# 408_jetracer_ledappend_boardRev010100.net
KiCad netlist of a schematic drawn in EAGLE
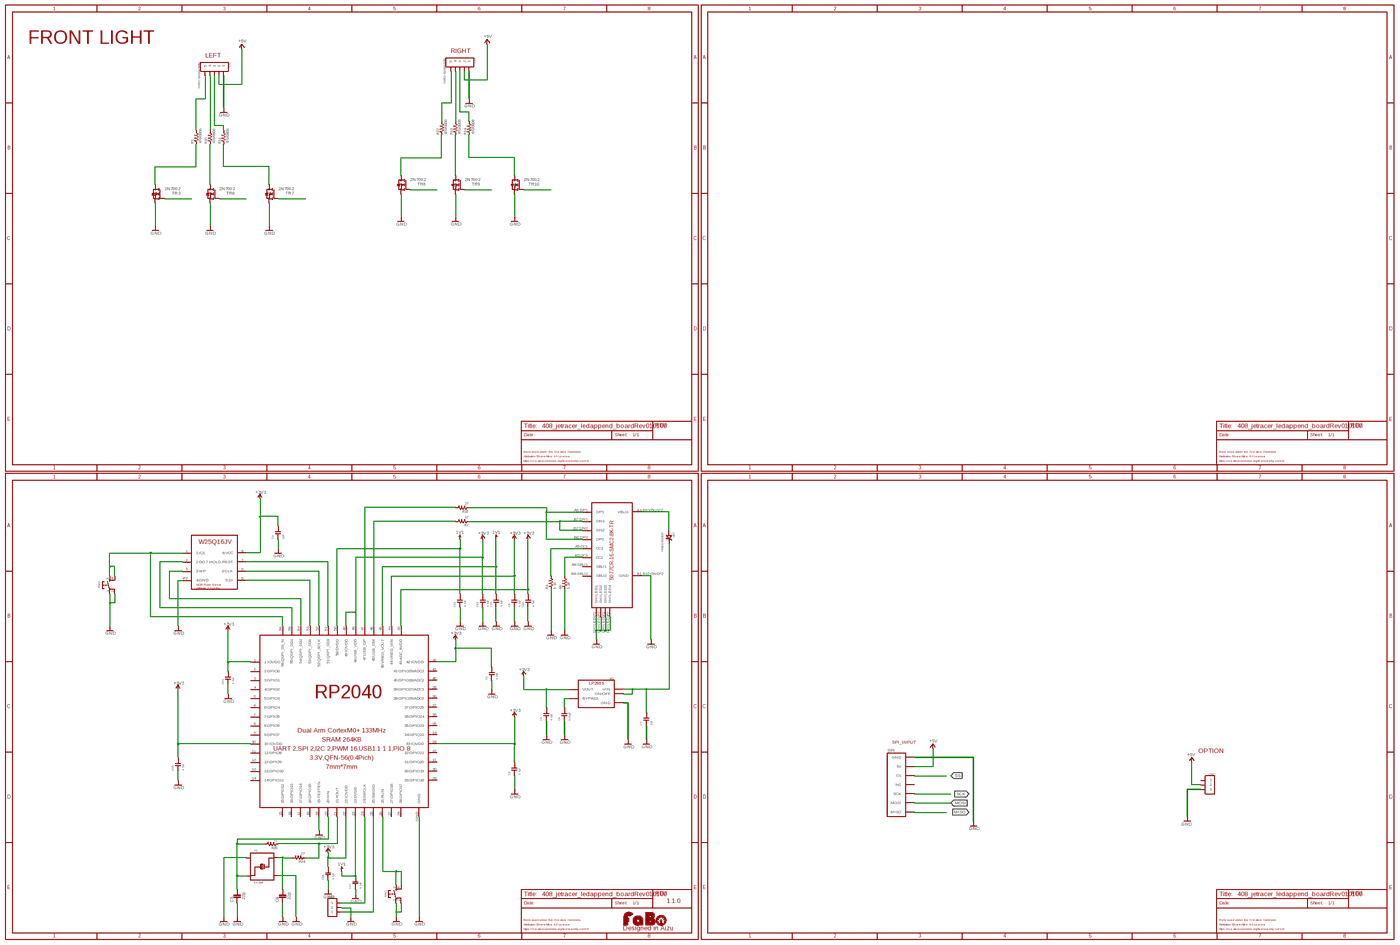
[diagram p0: schematic, sheet 1, overview]
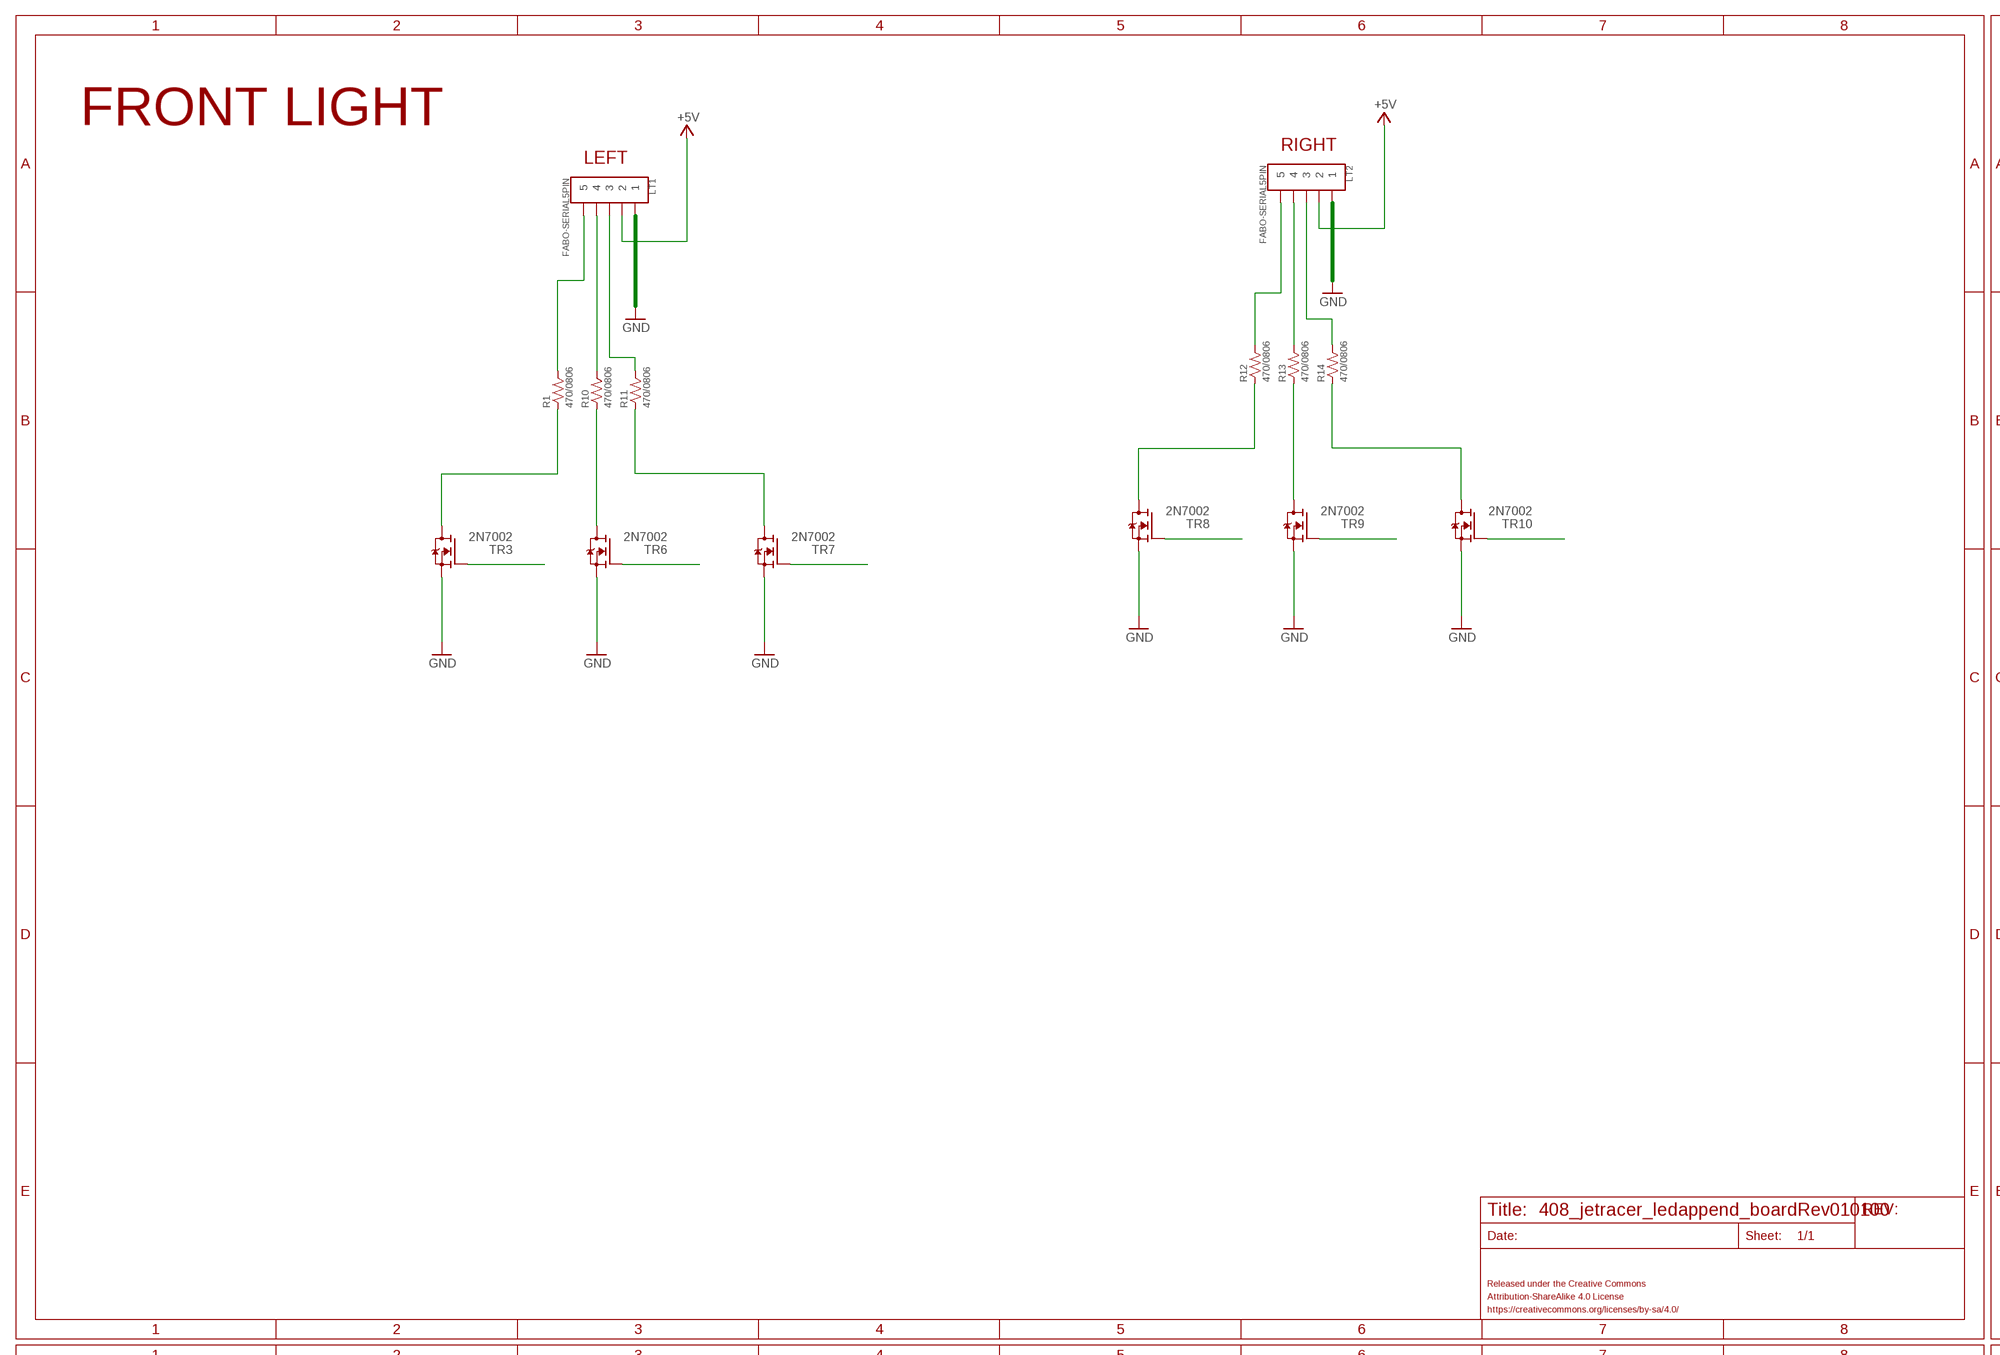
[diagram p1: schematic, sheet 1, part 1 of 4]
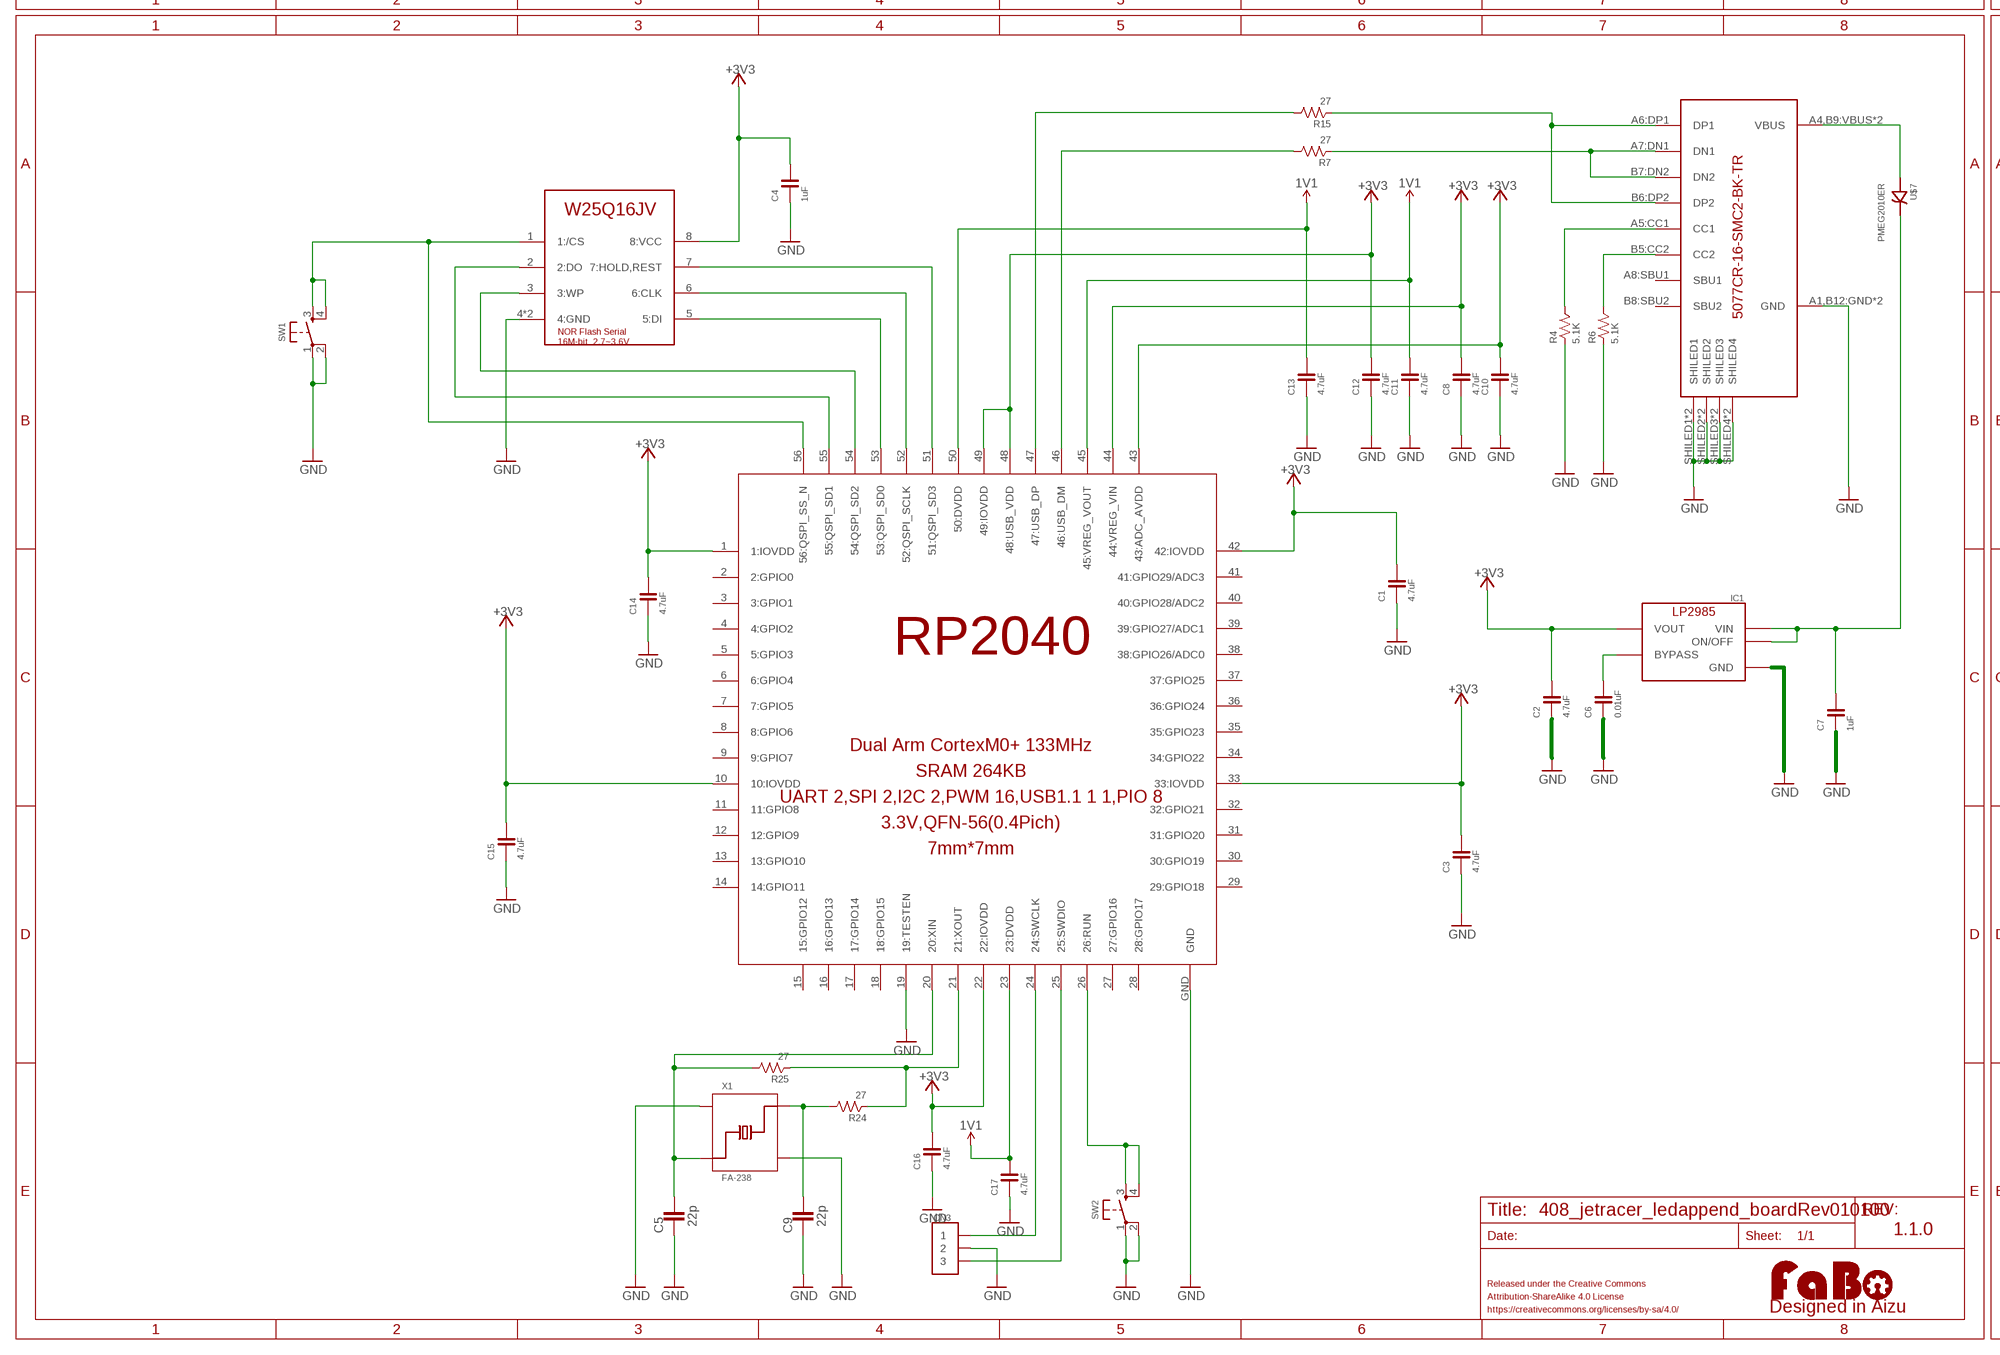
[diagram p2: schematic, sheet 1, part 2 of 4]
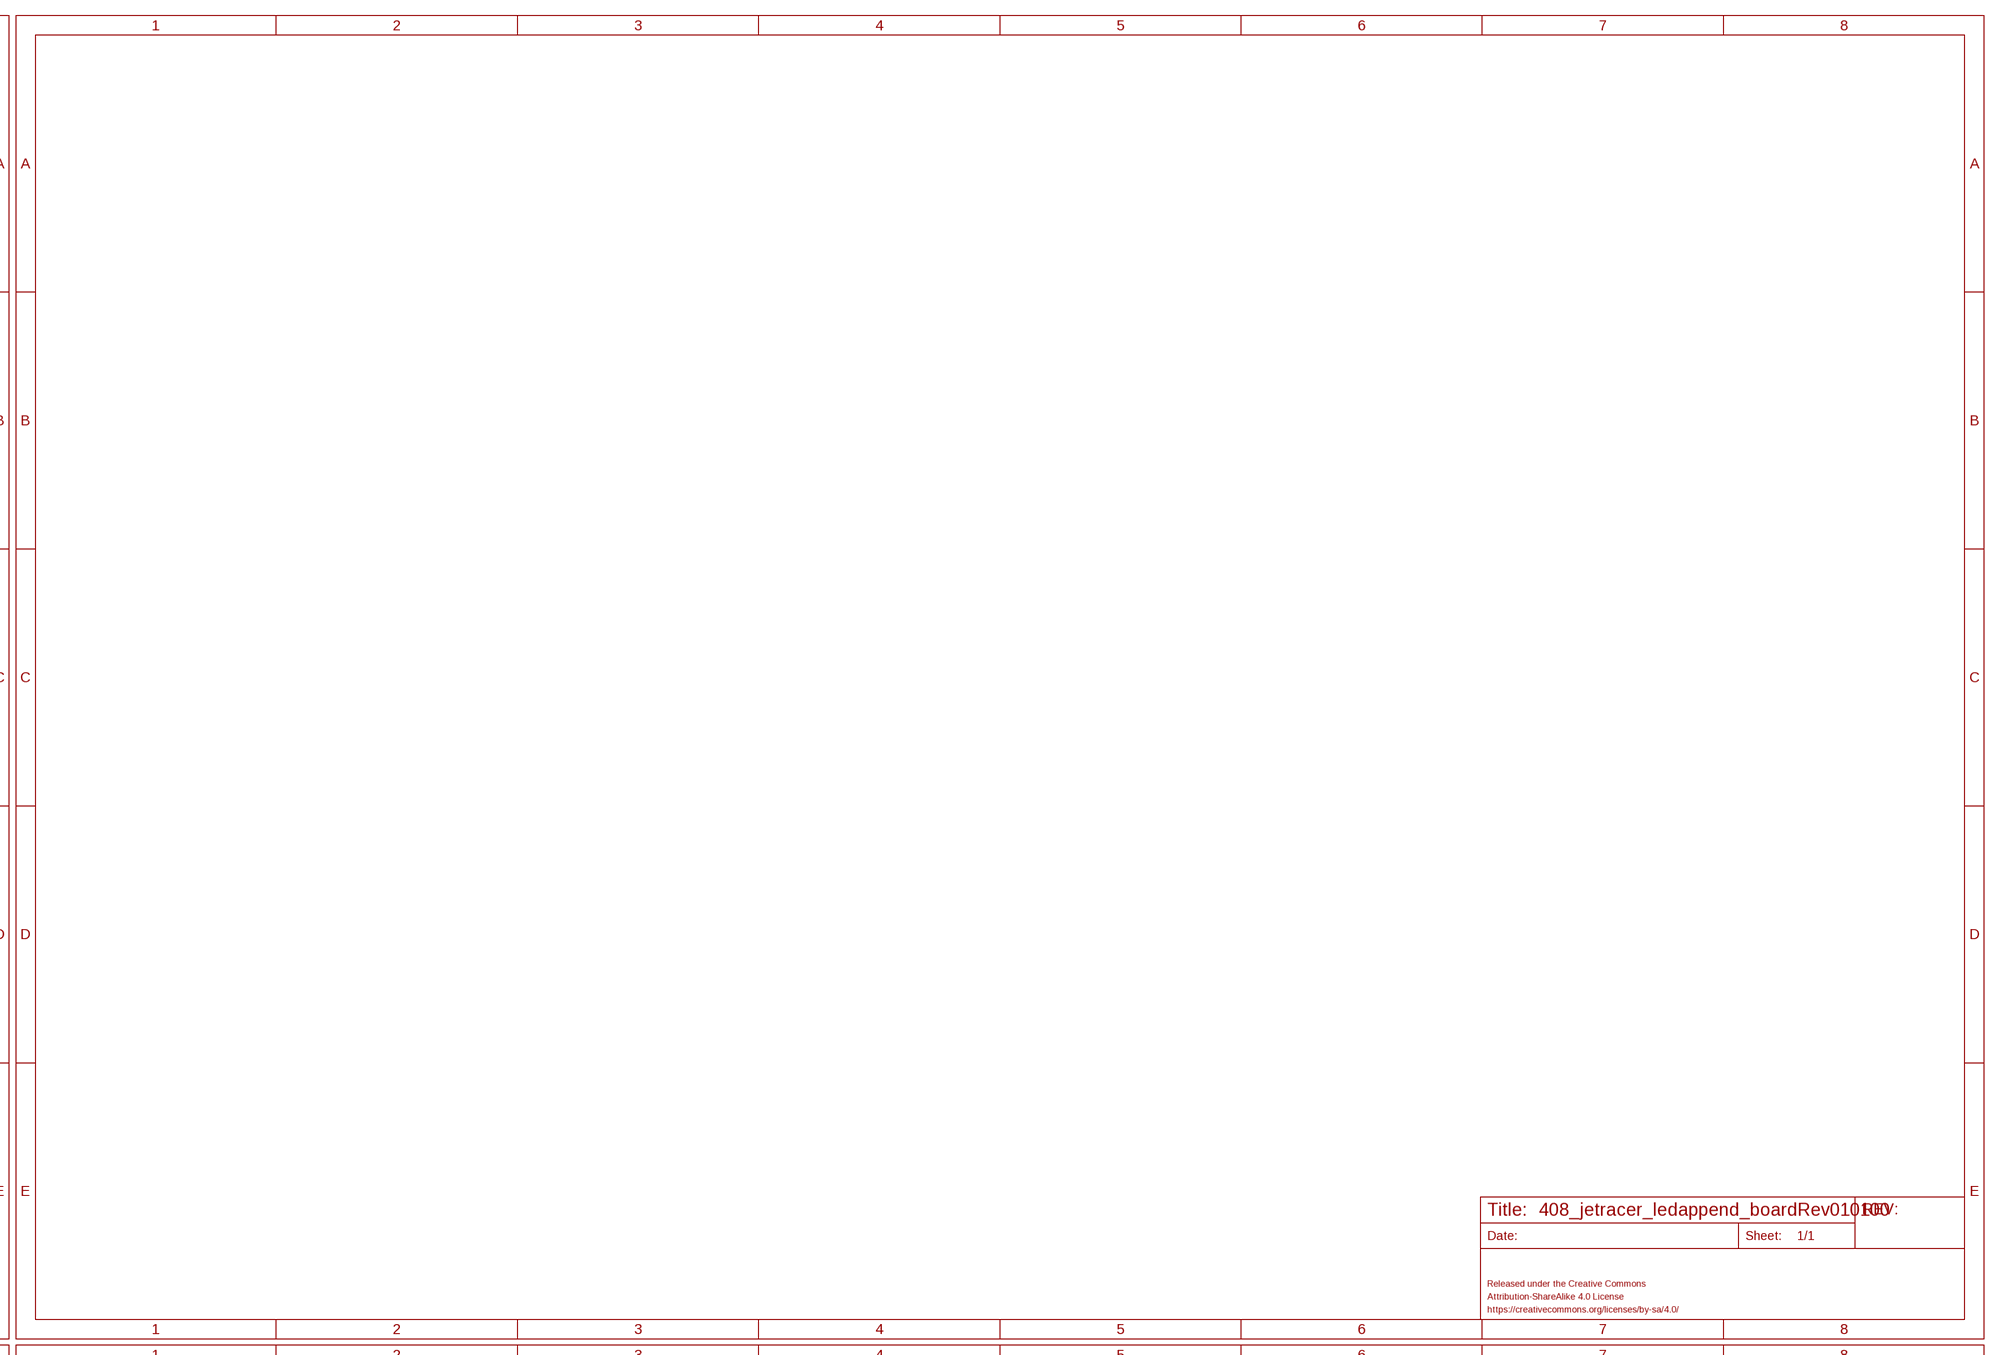
[diagram p3: schematic, sheet 1, part 3 of 4]
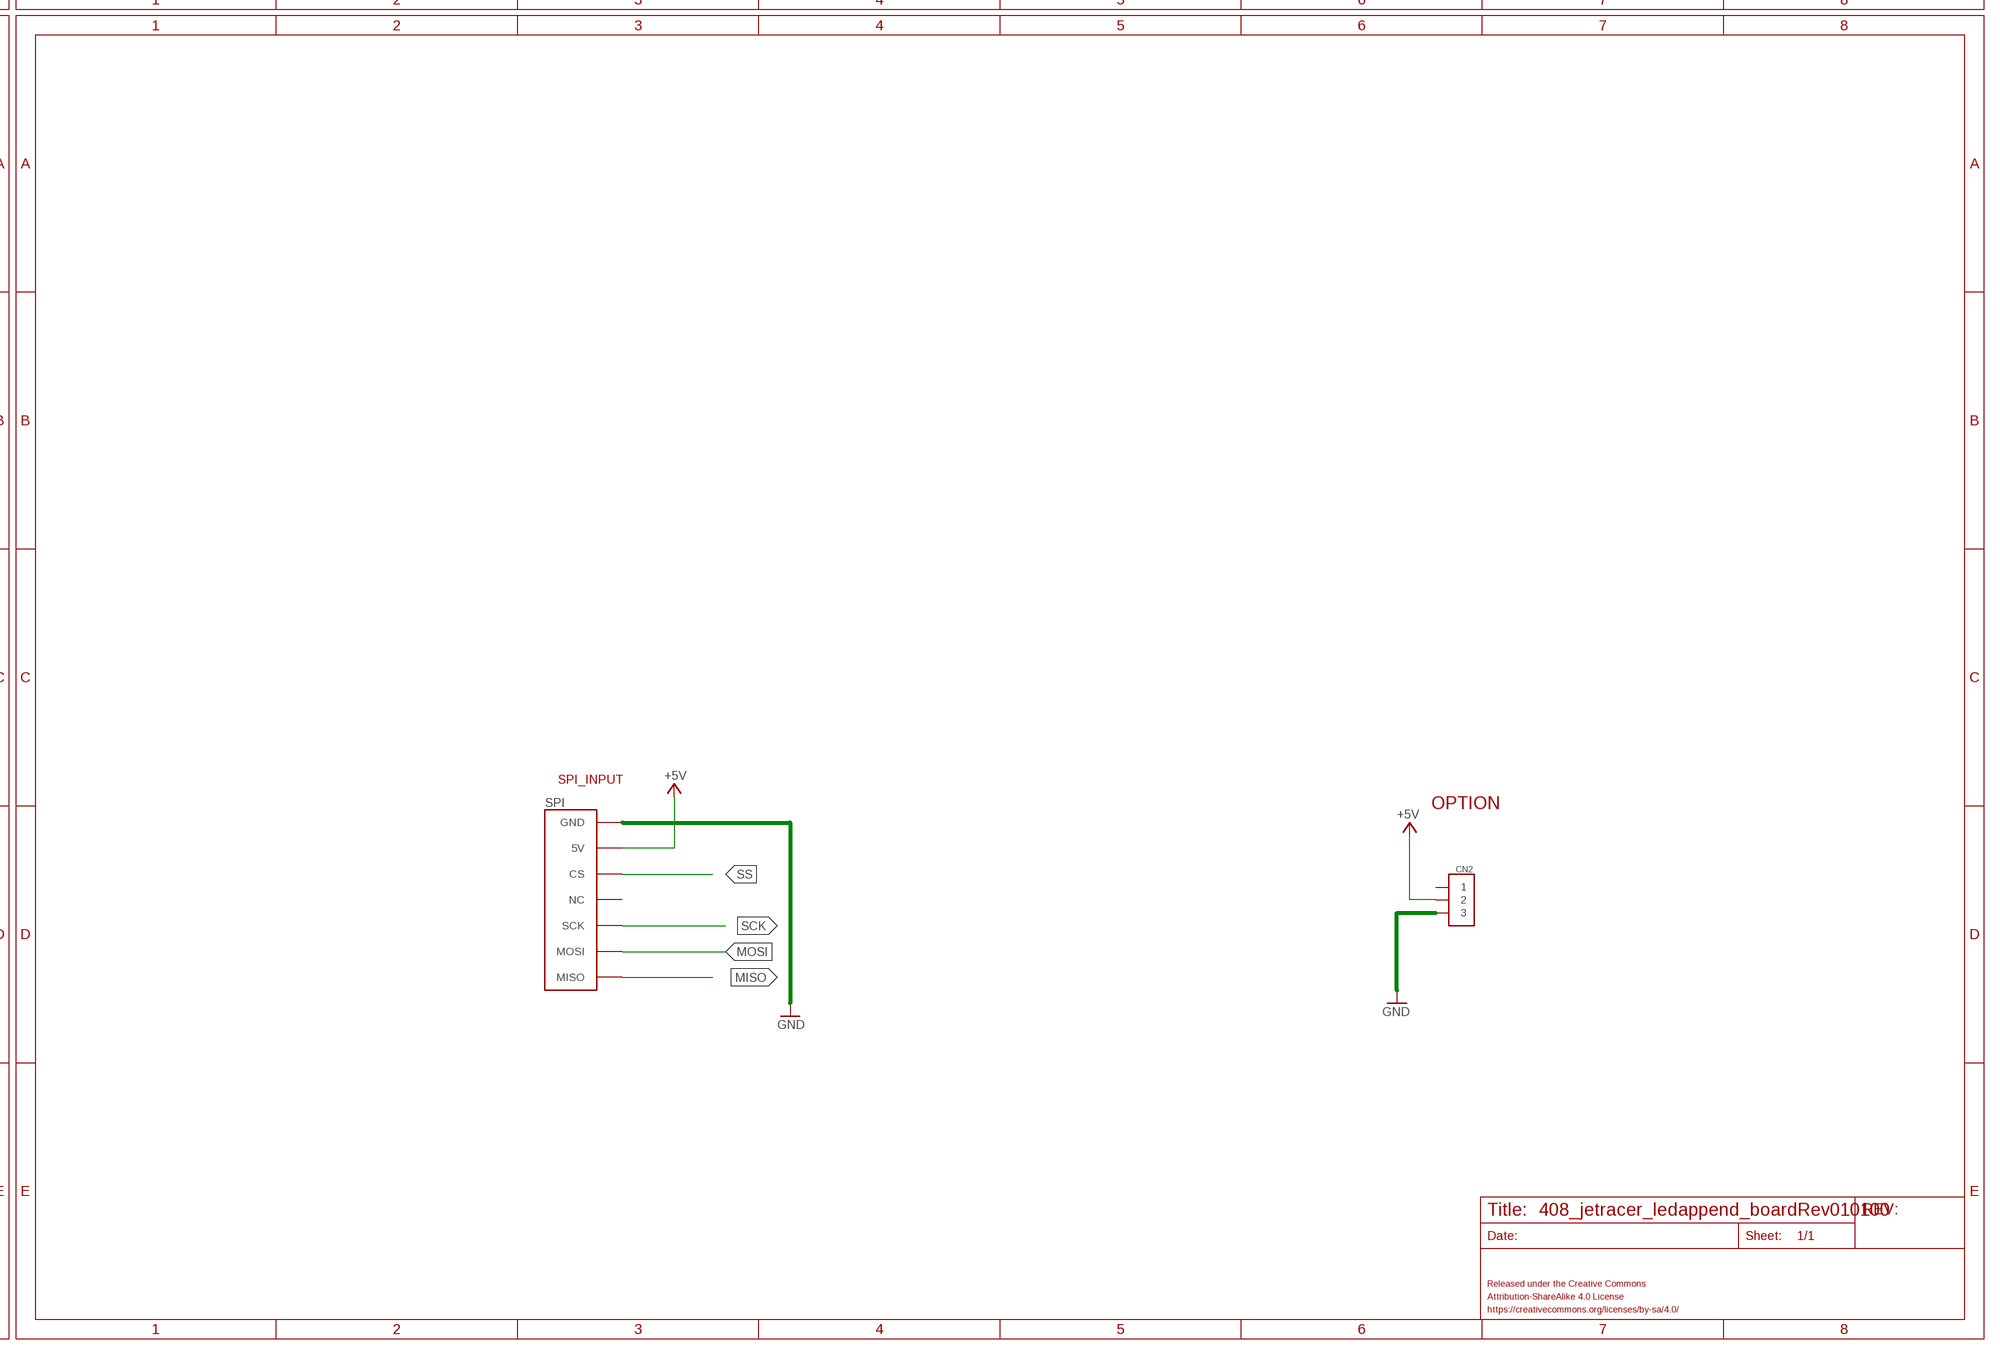
[diagram p4: schematic, sheet 1, part 4 of 4]

(export (version "E")
  (design (tool "Eeschema 10.0.6"))
  (components
    (comp (ref "C1")
      (value "4.7uF")
      (footprint "eagle-import:0603")
      (libsource (lib "eagle-import") (part "CAPACITOR-0603"))
    )
    (comp (ref "C2")
      (value "4.7uF")
      (footprint "eagle-import:0603")
      (libsource (lib "eagle-import") (part "CAPACITOR-0603"))
    )
    (comp (ref "C3")
      (value "4.7uF")
      (footprint "eagle-import:0603")
      (libsource (lib "eagle-import") (part "CAPACITOR-0603"))
    )
    (comp (ref "C4")
      (value "1uF")
      (footprint "eagle-import:0603")
      (libsource (lib "eagle-import") (part "CAPACITOR-0603"))
    )
    (comp (ref "C5")
      (value "22p")
      (footprint "eagle-import:C0603-ROUND")
      (fields (field (name "PART_NUMBER") "22pF_0603"))
      (libsource (lib "eagle-import") (part "0014_22PF_0603"))
    )
    (comp (ref "C6")
      (value "0.01uF")
      (footprint "eagle-import:0603")
      (libsource (lib "eagle-import") (part "CAPACITOR-0603"))
    )
    (comp (ref "C7")
      (value "1uF")
      (footprint "eagle-import:0603")
      (libsource (lib "eagle-import") (part "CAPACITOR-0603"))
    )
    (comp (ref "C8")
      (value "4.7uF")
      (footprint "eagle-import:0603")
      (libsource (lib "eagle-import") (part "CAPACITOR-0603"))
    )
    (comp (ref "C9")
      (value "22p")
      (footprint "eagle-import:C0603-ROUND")
      (fields (field (name "PART_NUMBER") "22pF_0603"))
      (libsource (lib "eagle-import") (part "0014_22PF_0603"))
    )
    (comp (ref "C10")
      (value "4.7uF")
      (footprint "eagle-import:0603")
      (libsource (lib "eagle-import") (part "CAPACITOR-0603"))
    )
    (comp (ref "C11")
      (value "4.7uF")
      (footprint "eagle-import:0603")
      (libsource (lib "eagle-import") (part "CAPACITOR-0603"))
    )
    (comp (ref "C12")
      (value "4.7uF")
      (footprint "eagle-import:0603")
      (libsource (lib "eagle-import") (part "CAPACITOR-0603"))
    )
    (comp (ref "C13")
      (value "4.7uF")
      (footprint "eagle-import:0603")
      (libsource (lib "eagle-import") (part "CAPACITOR-0603"))
    )
    (comp (ref "C14")
      (value "4.7uF")
      (footprint "eagle-import:0603")
      (libsource (lib "eagle-import") (part "CAPACITOR-0603"))
    )
    (comp (ref "C15")
      (value "4.7uF")
      (footprint "eagle-import:0603")
      (libsource (lib "eagle-import") (part "CAPACITOR-0603"))
    )
    (comp (ref "C16")
      (value "4.7uF")
      (footprint "eagle-import:0603")
      (libsource (lib "eagle-import") (part "CAPACITOR-0603"))
    )
    (comp (ref "C17")
      (value "4.7uF")
      (footprint "eagle-import:0603")
      (libsource (lib "eagle-import") (part "CAPACITOR-0603"))
    )
    (comp (ref "CN2")
      (value "PIN_1X3")
      (footprint "eagle-import:PIN_1X3")
      (libsource (lib "eagle-import") (part "PIN_1X3"))
    )
    (comp (ref "CN3")
      (value "PIN_1X3")
      (footprint "eagle-import:PIN_1X3")
      (libsource (lib "eagle-import") (part "PIN_1X3"))
    )
    (comp (ref "IC1")
      (value "LP2985-33DBV")
      (footprint "eagle-import:SOT-23-5")
      (libsource (lib "eagle-import") (part "LP2985-33DBV"))
    )
    (comp (ref "LOGO2")
      (value "LOGO_FABO-M_BOTTOM")
      (footprint "eagle-import:LOGO_FABO_M_BOTTOM")
      (libsource (lib "eagle-import") (part "LOGO_FABO-M_BOTTOM"))
    )
    (comp (ref "LT1")
      (value "FABO-SERIAL5PIN")
      (footprint "eagle-import:BM05B-PASS-1")
      (libsource (lib "eagle-import") (part "FABO-SERIAL5PIN"))
    )
    (comp (ref "LT2")
      (value "FABO-SERIAL5PIN")
      (footprint "eagle-import:BM05B-PASS-1")
      (libsource (lib "eagle-import") (part "FABO-SERIAL5PIN"))
    )
    (comp (ref "R1")
      (value "470/0806")
      (footprint "eagle-import:0805")
      (libsource (lib "eagle-import") (part "RESISTOR-0805"))
    )
    (comp (ref "R4")
      (value "5.1K")
      (footprint "eagle-import:0603")
      (libsource (lib "eagle-import") (part "RESISTOR-0603"))
    )
    (comp (ref "R6")
      (value "5.1K")
      (footprint "eagle-import:0603")
      (libsource (lib "eagle-import") (part "RESISTOR-0603"))
    )
    (comp (ref "R7")
      (value "27")
      (footprint "eagle-import:0603")
      (libsource (lib "eagle-import") (part "RESISTOR-0603"))
    )
    (comp (ref "R10")
      (value "470/0806")
      (footprint "eagle-import:0805")
      (libsource (lib "eagle-import") (part "RESISTOR-0805"))
    )
    (comp (ref "R11")
      (value "470/0806")
      (footprint "eagle-import:0805")
      (libsource (lib "eagle-import") (part "RESISTOR-0805"))
    )
    (comp (ref "R12")
      (value "470/0806")
      (footprint "eagle-import:0805")
      (libsource (lib "eagle-import") (part "RESISTOR-0805"))
    )
    (comp (ref "R13")
      (value "470/0806")
      (footprint "eagle-import:0805")
      (libsource (lib "eagle-import") (part "RESISTOR-0805"))
    )
    (comp (ref "R14")
      (value "470/0806")
      (footprint "eagle-import:0805")
      (libsource (lib "eagle-import") (part "RESISTOR-0805"))
    )
    (comp (ref "R15")
      (value "27")
      (footprint "eagle-import:0603")
      (libsource (lib "eagle-import") (part "RESISTOR-0603"))
    )
    (comp (ref "R24")
      (value "27")
      (footprint "eagle-import:0603")
      (libsource (lib "eagle-import") (part "RESISTOR-0603"))
    )
    (comp (ref "R25")
      (value "27")
      (footprint "eagle-import:0603")
      (libsource (lib "eagle-import") (part "RESISTOR-0603"))
    )
    (comp (ref "SPI")
      (value "FABO-7PINMULTI_SPI")
      (footprint "eagle-import:BM07B-PASS-1")
      (libsource (lib "eagle-import") (part "FABO-7PINMULTI_SPI"))
    )
    (comp (ref "SW1")
      (value "TACT-SWITCH-SMD_KMR2")
      (footprint "eagle-import:KMR2")
      (libsource (lib "eagle-import") (part "TACT-SWITCH-SMD_KMR2"))
    )
    (comp (ref "SW2")
      (value "TACT-SWITCH-SMD_KMR2")
      (footprint "eagle-import:KMR2")
      (libsource (lib "eagle-import") (part "TACT-SWITCH-SMD_KMR2"))
    )
    (comp (ref "TR3")
      (value "2N7002")
      (footprint "eagle-import:SOT-23")
      (libsource (lib "eagle-import") (part "1612_2N7002LT1G"))
    )
    (comp (ref "TR6")
      (value "2N7002")
      (footprint "eagle-import:SOT-23")
      (libsource (lib "eagle-import") (part "1612_2N7002LT1G"))
    )
    (comp (ref "TR7")
      (value "2N7002")
      (footprint "eagle-import:SOT-23")
      (libsource (lib "eagle-import") (part "1612_2N7002LT1G"))
    )
    (comp (ref "TR8")
      (value "2N7002")
      (footprint "eagle-import:SOT-23")
      (libsource (lib "eagle-import") (part "1612_2N7002LT1G"))
    )
    (comp (ref "TR9")
      (value "2N7002")
      (footprint "eagle-import:SOT-23")
      (libsource (lib "eagle-import") (part "1612_2N7002LT1G"))
    )
    (comp (ref "TR10")
      (value "2N7002")
      (footprint "eagle-import:SOT-23")
      (libsource (lib "eagle-import") (part "1612_2N7002LT1G"))
    )
    (comp (ref "U$2")
      (value "RP2040")
      (footprint "eagle-import:RP2040")
      (libsource (lib "eagle-import") (part "RP2040"))
    )
    (comp (ref "U$4")
      (value "W25Q16JVZPIM")
      (footprint "eagle-import:WSON8")
      (libsource (lib "eagle-import") (part "W25Q16JVZPIM"))
    )
    (comp (ref "U$6")
      (value "5077CR-16-SMC2-BK-TR")
      (footprint "eagle-import:5077CR-16-SMC2-BK-TR")
      (libsource (lib "eagle-import") (part "5077CR-16-SMC2-BK-TR"))
    )
    (comp (ref "U$7")
      (value "PMEG2010ER")
      (footprint "eagle-import:SOD123W")
      (libsource (lib "eagle-import") (part "PMEG2010ER"))
    )
    (comp (ref "X1")
      (value "FA-238")
      (footprint "eagle-import:FA-238")
      (libsource (lib "eagle-import") (part "FA-238"))
    )
  )
  (nets
    (net (code "1") (name "+3V3") (class "Default")
      (node (ref "C1") (pin "2") (pinfunction "2_2") (pintype "passive"))
      (node (ref "C10") (pin "2") (pinfunction "2_2") (pintype "passive"))
      (node (ref "C12") (pin "2") (pinfunction "2_2") (pintype "passive"))
      (node (ref "C14") (pin "2") (pinfunction "2_2") (pintype "passive"))
      (node (ref "C15") (pin "2") (pinfunction "2_2") (pintype "passive"))
      (node (ref "C16") (pin "2") (pinfunction "2_2") (pintype "passive"))
      (node (ref "C2") (pin "2") (pinfunction "2_2") (pintype "passive"))
      (node (ref "C3") (pin "2") (pinfunction "2_2") (pintype "passive"))
      (node (ref "C4") (pin "2") (pinfunction "2_2") (pintype "passive"))
      (node (ref "C8") (pin "2") (pinfunction "2_2") (pintype "passive"))
      (node (ref "IC1") (pin "5") (pinfunction "VOUT_5") (pintype "output"))
      (node (ref "U$2") (pin "1") (pinfunction "1:IOVDD_1") (pintype "bidirectional"))
      (node (ref "U$2") (pin "10") (pinfunction "10:IOVDD_10") (pintype "bidirectional"))
      (node (ref "U$2") (pin "22") (pinfunction "22:IOVDD_22") (pintype "bidirectional"))
      (node (ref "U$2") (pin "33") (pinfunction "33:IOVDD_33") (pintype "bidirectional"))
      (node (ref "U$2") (pin "42") (pinfunction "42:IOVDD_42") (pintype "bidirectional"))
      (node (ref "U$2") (pin "43") (pinfunction "43:ADC_AVDD_43") (pintype "bidirectional"))
      (node (ref "U$2") (pin "44") (pinfunction "44:VREG_VIN_44") (pintype "bidirectional"))
      (node (ref "U$2") (pin "48") (pinfunction "48:USB_VDD_48") (pintype "bidirectional"))
      (node (ref "U$2") (pin "49") (pinfunction "49:IOVDD_49") (pintype "bidirectional"))
      (node (ref "U$4") (pin "8") (pinfunction "8:VCC_8") (pintype "power_in"))
    )
    (net (code "2") (name "+5V") (class "Default")
      (node (ref "CN2") (pin "2") (pinfunction "2_2") (pintype "bidirectional"))
      (node (ref "LT1") (pin "2") (pinfunction "2_2") (pintype "bidirectional"))
      (node (ref "LT2") (pin "2") (pinfunction "2_2") (pintype "bidirectional"))
      (node (ref "SPI") (pin "2") (pinfunction "5V_2") (pintype "bidirectional"))
    )
    (net (code "3") (name "/N$10") (class "Default")
      (node (ref "TR10") (pin "3") (pinfunction "G_3") (pintype "passive"))
      (node (ref "TR3") (pin "3") (pinfunction "G_3") (pintype "passive"))
      (node (ref "TR6") (pin "3") (pinfunction "G_3") (pintype "passive"))
      (node (ref "TR7") (pin "3") (pinfunction "G_3") (pintype "passive"))
      (node (ref "TR8") (pin "3") (pinfunction "G_3") (pintype "passive"))
      (node (ref "TR9") (pin "3") (pinfunction "G_3") (pintype "passive"))
    )
    (net (code "4") (name "1V1") (class "Default")
      (node (ref "C11") (pin "2") (pinfunction "2_2") (pintype "passive"))
      (node (ref "C13") (pin "2") (pinfunction "2_2") (pintype "passive"))
      (node (ref "C17") (pin "2") (pinfunction "2_2") (pintype "passive"))
      (node (ref "U$2") (pin "23") (pinfunction "23:DVDD_23") (pintype "bidirectional"))
      (node (ref "U$2") (pin "45") (pinfunction "45:VREG_VOUT_45") (pintype "bidirectional"))
      (node (ref "U$2") (pin "50") (pinfunction "50:DVDD_50") (pintype "bidirectional"))
    )
    (net (code "5") (name "GND") (class "Default")
      (node (ref "C1") (pin "1") (pinfunction "1_1") (pintype "passive"))
      (node (ref "C10") (pin "1") (pinfunction "1_1") (pintype "passive"))
      (node (ref "C11") (pin "1") (pinfunction "1_1") (pintype "passive"))
      (node (ref "C12") (pin "1") (pinfunction "1_1") (pintype "passive"))
      (node (ref "C13") (pin "1") (pinfunction "1_1") (pintype "passive"))
      (node (ref "C14") (pin "1") (pinfunction "1_1") (pintype "passive"))
      (node (ref "C15") (pin "1") (pinfunction "1_1") (pintype "passive"))
      (node (ref "C16") (pin "1") (pinfunction "1_1") (pintype "passive"))
      (node (ref "C17") (pin "1") (pinfunction "1_1") (pintype "passive"))
      (node (ref "C2") (pin "1") (pinfunction "1_1") (pintype "passive"))
      (node (ref "C3") (pin "1") (pinfunction "1_1") (pintype "passive"))
      (node (ref "C4") (pin "1") (pinfunction "1_1") (pintype "passive"))
      (node (ref "C5") (pin "1") (pinfunction "1_1") (pintype "passive"))
      (node (ref "C6") (pin "1") (pinfunction "1_1") (pintype "passive"))
      (node (ref "C7") (pin "1") (pinfunction "1_1") (pintype "passive"))
      (node (ref "C8") (pin "1") (pinfunction "1_1") (pintype "passive"))
      (node (ref "C9") (pin "1") (pinfunction "1_1") (pintype "passive"))
      (node (ref "CN2") (pin "3") (pinfunction "3_3") (pintype "bidirectional"))
      (node (ref "CN3") (pin "2") (pinfunction "2_2") (pintype "bidirectional"))
      (node (ref "IC1") (pin "2") (pinfunction "GND_2") (pintype "power_in"))
      (node (ref "LT1") (pin "1") (pinfunction "1_1") (pintype "bidirectional"))
      (node (ref "LT2") (pin "1") (pinfunction "1_1") (pintype "bidirectional"))
      (node (ref "R4") (pin "1") (pinfunction "1_1") (pintype "bidirectional"))
      (node (ref "R6") (pin "1") (pinfunction "1_1") (pintype "bidirectional"))
      (node (ref "SPI") (pin "1") (pinfunction "GND_1") (pintype "bidirectional"))
      (node (ref "SW1") (pin "1") (pinfunction "1_1") (pintype "passive"))
      (node (ref "SW1") (pin "2") (pinfunction "2_2") (pintype "passive"))
      (node (ref "SW2") (pin "1") (pinfunction "1_1") (pintype "passive"))
      (node (ref "SW2") (pin "2") (pinfunction "2_2") (pintype "passive"))
      (node (ref "TR10") (pin "2") (pinfunction "S_2") (pintype "passive"))
      (node (ref "TR3") (pin "2") (pinfunction "S_2") (pintype "passive"))
      (node (ref "TR6") (pin "2") (pinfunction "S_2") (pintype "passive"))
      (node (ref "TR7") (pin "2") (pinfunction "S_2") (pintype "passive"))
      (node (ref "TR8") (pin "2") (pinfunction "S_2") (pintype "passive"))
      (node (ref "TR9") (pin "2") (pinfunction "S_2") (pintype "passive"))
      (node (ref "U$2") (pin "19") (pinfunction "19:TESTEN_19") (pintype "bidirectional"))
      (node (ref "U$2") (pin "GND") (pinfunction "GND_GND") (pintype "bidirectional"))
      (node (ref "U$4") (pin "4") (pinfunction "4:GND_4") (pintype "power_in"))
      (node (ref "U$4") (pin "PAD") (pinfunction "4:GND_PAD") (pintype "power_in"))
      (node (ref "U$6") (pin "A1,B12:GND") (pinfunction "GND_A1,B12:GND") (pintype "power_in"))
      (node (ref "U$6") (pin "B1,A12:GND") (pinfunction "GND_B1,A12:GND") (pintype "power_in"))
      (node (ref "U$6") (pin "SHILED1") (pinfunction "SHILED1_SHILED1") (pintype "bidirectional"))
      (node (ref "U$6") (pin "SHILED2") (pinfunction "SHILED2_SHILED2") (pintype "bidirectional"))
      (node (ref "U$6") (pin "SHILED3") (pinfunction "SHILED3_SHILED3") (pintype "bidirectional"))
      (node (ref "U$6") (pin "SHILED4") (pinfunction "SHILED4_SHILED4") (pintype "bidirectional"))
      (node (ref "U$6") (pin "SHILED5") (pinfunction "SHILED1_SHILED5") (pintype "bidirectional"))
      (node (ref "U$6") (pin "SHILED6") (pinfunction "SHILED2_SHILED6") (pintype "bidirectional"))
      (node (ref "U$6") (pin "SHILED7") (pinfunction "SHILED3_SHILED7") (pintype "bidirectional"))
      (node (ref "U$6") (pin "SHILED8") (pinfunction "SHILED4_SHILED8") (pintype "bidirectional"))
      (node (ref "X1") (pin "2") (pinfunction "#2_2") (pintype "bidirectional"))
      (node (ref "X1") (pin "4") (pinfunction "#4_4") (pintype "bidirectional"))
    )
    (net (code "6") (name "MISO") (class "Default")
      (node (ref "SPI") (pin "7") (pinfunction "MISO_7") (pintype "bidirectional"))
    )
    (net (code "7") (name "MOSI") (class "Default")
      (node (ref "SPI") (pin "6") (pinfunction "MOSI_6") (pintype "bidirectional"))
    )
    (net (code "8") (name "Net-(IC1-BYPASS)") (class "Default")
      (node (ref "C6") (pin "2") (pinfunction "2_2") (pintype "passive"))
      (node (ref "IC1") (pin "4") (pinfunction "BYPASS_4") (pintype "bidirectional"))
    )
    (net (code "9") (name "Net-(IC1-ON{slash}OFF)") (class "Default")
      (node (ref "C7") (pin "2") (pinfunction "2_2") (pintype "passive"))
      (node (ref "IC1") (pin "1") (pinfunction "VIN_1") (pintype "input"))
      (node (ref "IC1") (pin "3") (pinfunction "ON/OFF_3") (pintype "input"))
      (node (ref "U$7") (pin "1") (pinfunction "CATHODE_1") (pintype "bidirectional"))
    )
    (net (code "10") (name "Net-(LT1-Pad3)") (class "Default")
      (node (ref "LT1") (pin "3") (pinfunction "3_3") (pintype "bidirectional"))
      (node (ref "R11") (pin "2") (pinfunction "2_2") (pintype "bidirectional"))
    )
    (net (code "11") (name "Net-(LT1-Pad4)") (class "Default")
      (node (ref "LT1") (pin "4") (pinfunction "4_4") (pintype "bidirectional"))
      (node (ref "R10") (pin "2") (pinfunction "2_2") (pintype "bidirectional"))
    )
    (net (code "12") (name "Net-(LT1-Pad5)") (class "Default")
      (node (ref "LT1") (pin "5") (pinfunction "5_5") (pintype "bidirectional"))
      (node (ref "R1") (pin "2") (pinfunction "2_2") (pintype "bidirectional"))
    )
    (net (code "13") (name "Net-(LT2-Pad3)") (class "Default")
      (node (ref "LT2") (pin "3") (pinfunction "3_3") (pintype "bidirectional"))
      (node (ref "R14") (pin "2") (pinfunction "2_2") (pintype "bidirectional"))
    )
    (net (code "14") (name "Net-(LT2-Pad4)") (class "Default")
      (node (ref "LT2") (pin "4") (pinfunction "4_4") (pintype "bidirectional"))
      (node (ref "R13") (pin "2") (pinfunction "2_2") (pintype "bidirectional"))
    )
    (net (code "15") (name "Net-(LT2-Pad5)") (class "Default")
      (node (ref "LT2") (pin "5") (pinfunction "5_5") (pintype "bidirectional"))
      (node (ref "R12") (pin "2") (pinfunction "2_2") (pintype "bidirectional"))
    )
    (net (code "16") (name "Net-(TR3-D)") (class "Default")
      (node (ref "R1") (pin "1") (pinfunction "1_1") (pintype "bidirectional"))
      (node (ref "TR3") (pin "1") (pinfunction "D_1") (pintype "passive"))
    )
    (net (code "17") (name "Net-(TR6-D)") (class "Default")
      (node (ref "R10") (pin "1") (pinfunction "1_1") (pintype "bidirectional"))
      (node (ref "TR6") (pin "1") (pinfunction "D_1") (pintype "passive"))
    )
    (net (code "18") (name "Net-(TR7-D)") (class "Default")
      (node (ref "R11") (pin "1") (pinfunction "1_1") (pintype "bidirectional"))
      (node (ref "TR7") (pin "1") (pinfunction "D_1") (pintype "passive"))
    )
    (net (code "19") (name "Net-(TR8-D)") (class "Default")
      (node (ref "R12") (pin "1") (pinfunction "1_1") (pintype "bidirectional"))
      (node (ref "TR8") (pin "1") (pinfunction "D_1") (pintype "passive"))
    )
    (net (code "20") (name "Net-(TR9-D)") (class "Default")
      (node (ref "R13") (pin "1") (pinfunction "1_1") (pintype "bidirectional"))
      (node (ref "TR9") (pin "1") (pinfunction "D_1") (pintype "passive"))
    )
    (net (code "21") (name "Net-(TR10-D)") (class "Default")
      (node (ref "R14") (pin "1") (pinfunction "1_1") (pintype "bidirectional"))
      (node (ref "TR10") (pin "1") (pinfunction "D_1") (pintype "passive"))
    )
    (net (code "22") (name "Net-(U$2-20:XIN)") (class "Default")
      (node (ref "C5") (pin "2") (pinfunction "2_2") (pintype "passive"))
      (node (ref "R25") (pin "2") (pinfunction "2_2") (pintype "bidirectional"))
      (node (ref "U$2") (pin "20") (pinfunction "20:XIN_20") (pintype "bidirectional"))
      (node (ref "X1") (pin "1") (pinfunction "#1_1") (pintype "bidirectional"))
    )
    (net (code "23") (name "Net-(U$2-21:XOUT)") (class "Default")
      (node (ref "R24") (pin "1") (pinfunction "1_1") (pintype "bidirectional"))
      (node (ref "R25") (pin "1") (pinfunction "1_1") (pintype "bidirectional"))
      (node (ref "U$2") (pin "21") (pinfunction "21:XOUT_21") (pintype "bidirectional"))
    )
    (net (code "24") (name "Net-(U$2-24:SWCLK)") (class "Default")
      (node (ref "CN3") (pin "1") (pinfunction "1_1") (pintype "bidirectional"))
      (node (ref "U$2") (pin "24") (pinfunction "24:SWCLK_24") (pintype "bidirectional"))
    )
    (net (code "25") (name "Net-(U$2-25:SWDIO)") (class "Default")
      (node (ref "CN3") (pin "3") (pinfunction "3_3") (pintype "bidirectional"))
      (node (ref "U$2") (pin "25") (pinfunction "25:SWDIO_25") (pintype "bidirectional"))
    )
    (net (code "26") (name "Net-(U$2-26:RUN)") (class "Default")
      (node (ref "SW2") (pin "3") (pinfunction "3_3") (pintype "passive"))
      (node (ref "SW2") (pin "4") (pinfunction "4_4") (pintype "passive"))
      (node (ref "U$2") (pin "26") (pinfunction "26:RUN_26") (pintype "bidirectional"))
    )
    (net (code "27") (name "Net-(U$2-46:USB_DM)") (class "Default")
      (node (ref "R7") (pin "2") (pinfunction "2_2") (pintype "bidirectional"))
      (node (ref "U$2") (pin "46") (pinfunction "46:USB_DM_46") (pintype "bidirectional"))
    )
    (net (code "28") (name "Net-(U$2-47:USB_DP)") (class "Default")
      (node (ref "R15") (pin "2") (pinfunction "2_2") (pintype "bidirectional"))
      (node (ref "U$2") (pin "47") (pinfunction "47:USB_DP_47") (pintype "bidirectional"))
    )
    (net (code "29") (name "Net-(U$2-51:QSPI_SD3)") (class "Default")
      (node (ref "U$2") (pin "51") (pinfunction "51:QSPI_SD3_51") (pintype "bidirectional"))
      (node (ref "U$4") (pin "7") (pinfunction "7:HOLD,REST_7") (pintype "bidirectional"))
    )
    (net (code "30") (name "Net-(U$2-52:QSPI_SCLK)") (class "Default")
      (node (ref "U$2") (pin "52") (pinfunction "52:QSPI_SCLK_52") (pintype "bidirectional"))
      (node (ref "U$4") (pin "6") (pinfunction "6:CLK_6") (pintype "input"))
    )
    (net (code "31") (name "Net-(U$2-53:QSPI_SD0)") (class "Default")
      (node (ref "U$2") (pin "53") (pinfunction "53:QSPI_SD0_53") (pintype "bidirectional"))
      (node (ref "U$4") (pin "5") (pinfunction "5:DI_5") (pintype "bidirectional"))
    )
    (net (code "32") (name "Net-(U$2-54:QSPI_SD2)") (class "Default")
      (node (ref "U$2") (pin "54") (pinfunction "54:QSPI_SD2_54") (pintype "bidirectional"))
      (node (ref "U$4") (pin "3") (pinfunction "3:WP_3") (pintype "bidirectional"))
    )
    (net (code "33") (name "Net-(U$2-55:QSPI_SD1)") (class "Default")
      (node (ref "U$2") (pin "55") (pinfunction "55:QSPI_SD1_55") (pintype "bidirectional"))
      (node (ref "U$4") (pin "2") (pinfunction "2:DO_2") (pintype "output"))
    )
    (net (code "34") (name "Net-(U$2-56:QSPI_SS_N)") (class "Default")
      (node (ref "SW1") (pin "3") (pinfunction "3_3") (pintype "passive"))
      (node (ref "SW1") (pin "4") (pinfunction "4_4") (pintype "passive"))
      (node (ref "U$2") (pin "56") (pinfunction "56:QSPI_SS_N_56") (pintype "bidirectional"))
      (node (ref "U$4") (pin "1") (pinfunction "1:/CS_1") (pintype "input"))
    )
    (net (code "35") (name "Net-(U$6-CC1)") (class "Default")
      (node (ref "R4") (pin "2") (pinfunction "2_2") (pintype "bidirectional"))
      (node (ref "U$6") (pin "A5:CC1") (pinfunction "CC1_A5:CC1") (pintype "bidirectional"))
    )
    (net (code "36") (name "Net-(U$6-CC2)") (class "Default")
      (node (ref "R6") (pin "2") (pinfunction "2_2") (pintype "bidirectional"))
      (node (ref "U$6") (pin "B5:CC2") (pinfunction "CC2_B5:CC2") (pintype "bidirectional"))
    )
    (net (code "37") (name "Net-(U$6-DN1)") (class "Default")
      (node (ref "R7") (pin "1") (pinfunction "1_1") (pintype "bidirectional"))
      (node (ref "U$6") (pin "A7:DN1") (pinfunction "DN1_A7:DN1") (pintype "bidirectional"))
      (node (ref "U$6") (pin "B7:DN2") (pinfunction "DN2_B7:DN2") (pintype "bidirectional"))
    )
    (net (code "38") (name "Net-(U$6-DP1)") (class "Default")
      (node (ref "R15") (pin "1") (pinfunction "1_1") (pintype "bidirectional"))
      (node (ref "U$6") (pin "A6:DP1") (pinfunction "DP1_A6:DP1") (pintype "bidirectional"))
      (node (ref "U$6") (pin "B6:DP2") (pinfunction "DP2_B6:DP2") (pintype "bidirectional"))
    )
    (net (code "39") (name "Net-(U$7-ANODE)") (class "Default")
      (node (ref "U$6") (pin "A4,B9:VBUS") (pinfunction "VBUS_A4,B9:VBUS") (pintype "power_in"))
      (node (ref "U$6") (pin "B4,A9:VBUS") (pinfunction "VBUS_B4,A9:VBUS") (pintype "power_in"))
      (node (ref "U$7") (pin "2") (pinfunction "ANODE_2") (pintype "bidirectional"))
    )
    (net (code "40") (name "Net-(X1-#3)") (class "Default")
      (node (ref "C9") (pin "2") (pinfunction "2_2") (pintype "passive"))
      (node (ref "R24") (pin "2") (pinfunction "2_2") (pintype "bidirectional"))
      (node (ref "X1") (pin "3") (pinfunction "#3_3") (pintype "bidirectional"))
    )
    (net (code "41") (name "SCK") (class "Default")
      (node (ref "SPI") (pin "5") (pinfunction "SCK_5") (pintype "bidirectional"))
    )
    (net (code "42") (name "SS") (class "Default")
      (node (ref "SPI") (pin "3") (pinfunction "CS_3") (pintype "bidirectional"))
    )
    (net (code "43") (name "unconnected-(CN2-Pad1)") (class "Default")
      (node (ref "CN2") (pin "1") (pinfunction "1_1") (pintype "bidirectional"))
    )
    (net (code "44") (name "unconnected-(SPI-NC-Pad4)") (class "Default")
      (node (ref "SPI") (pin "4") (pinfunction "NC_4") (pintype "bidirectional"))
    )
    (net (code "45") (name "unconnected-(U$2-2:GPIO0-Pad2)") (class "Default")
      (node (ref "U$2") (pin "2") (pinfunction "2:GPIO0_2") (pintype "bidirectional"))
    )
    (net (code "46") (name "unconnected-(U$2-3:GPIO1-Pad3)") (class "Default")
      (node (ref "U$2") (pin "3") (pinfunction "3:GPIO1_3") (pintype "bidirectional"))
    )
    (net (code "47") (name "unconnected-(U$2-4:GPIO2-Pad4)") (class "Default")
      (node (ref "U$2") (pin "4") (pinfunction "4:GPIO2_4") (pintype "bidirectional"))
    )
    (net (code "48") (name "unconnected-(U$2-5:GPIO3-Pad5)") (class "Default")
      (node (ref "U$2") (pin "5") (pinfunction "5:GPIO3_5") (pintype "bidirectional"))
    )
    (net (code "49") (name "unconnected-(U$2-6:GPIO4-Pad6)") (class "Default")
      (node (ref "U$2") (pin "6") (pinfunction "6:GPIO4_6") (pintype "bidirectional"))
    )
    (net (code "50") (name "unconnected-(U$2-7:GPIO5-Pad7)") (class "Default")
      (node (ref "U$2") (pin "7") (pinfunction "7:GPIO5_7") (pintype "bidirectional"))
    )
    (net (code "51") (name "unconnected-(U$2-8:GPIO6-Pad8)") (class "Default")
      (node (ref "U$2") (pin "8") (pinfunction "8:GPIO6_8") (pintype "bidirectional"))
    )
    (net (code "52") (name "unconnected-(U$2-9:GPIO7-Pad9)") (class "Default")
      (node (ref "U$2") (pin "9") (pinfunction "9:GPIO7_9") (pintype "bidirectional"))
    )
    (net (code "53") (name "unconnected-(U$2-11:GPIO8-Pad11)") (class "Default")
      (node (ref "U$2") (pin "11") (pinfunction "11:GPIO8_11") (pintype "bidirectional"))
    )
    (net (code "54") (name "unconnected-(U$2-12:GPIO9-Pad12)") (class "Default")
      (node (ref "U$2") (pin "12") (pinfunction "12:GPIO9_12") (pintype "bidirectional"))
    )
    (net (code "55") (name "unconnected-(U$2-13:GPIO10-Pad13)") (class "Default")
      (node (ref "U$2") (pin "13") (pinfunction "13:GPIO10_13") (pintype "bidirectional"))
    )
    (net (code "56") (name "unconnected-(U$2-14:GPIO11-Pad14)") (class "Default")
      (node (ref "U$2") (pin "14") (pinfunction "14:GPIO11_14") (pintype "bidirectional"))
    )
    (net (code "57") (name "unconnected-(U$2-15:GPIO12-Pad15)") (class "Default")
      (node (ref "U$2") (pin "15") (pinfunction "15:GPIO12_15") (pintype "bidirectional"))
    )
    (net (code "58") (name "unconnected-(U$2-16:GPIO13-Pad16)") (class "Default")
      (node (ref "U$2") (pin "16") (pinfunction "16:GPIO13_16") (pintype "bidirectional"))
    )
    (net (code "59") (name "unconnected-(U$2-17:GPIO14-Pad17)") (class "Default")
      (node (ref "U$2") (pin "17") (pinfunction "17:GPIO14_17") (pintype "bidirectional"))
    )
    (net (code "60") (name "unconnected-(U$2-18:GPIO15-Pad18)") (class "Default")
      (node (ref "U$2") (pin "18") (pinfunction "18:GPIO15_18") (pintype "bidirectional"))
    )
    (net (code "61") (name "unconnected-(U$2-27:GPIO16-Pad27)") (class "Default")
      (node (ref "U$2") (pin "27") (pinfunction "27:GPIO16_27") (pintype "bidirectional"))
    )
    (net (code "62") (name "unconnected-(U$2-28:GPIO17-Pad28)") (class "Default")
      (node (ref "U$2") (pin "28") (pinfunction "28:GPIO17_28") (pintype "bidirectional"))
    )
    (net (code "63") (name "unconnected-(U$2-29:GPIO18-Pad29)") (class "Default")
      (node (ref "U$2") (pin "29") (pinfunction "29:GPIO18_29") (pintype "bidirectional"))
    )
    (net (code "64") (name "unconnected-(U$2-30:GPIO19-Pad30)") (class "Default")
      (node (ref "U$2") (pin "30") (pinfunction "30:GPIO19_30") (pintype "bidirectional"))
    )
    (net (code "65") (name "unconnected-(U$2-31:GPIO20-Pad31)") (class "Default")
      (node (ref "U$2") (pin "31") (pinfunction "31:GPIO20_31") (pintype "bidirectional"))
    )
    (net (code "66") (name "unconnected-(U$2-32:GPIO21-Pad32)") (class "Default")
      (node (ref "U$2") (pin "32") (pinfunction "32:GPIO21_32") (pintype "bidirectional"))
    )
    (net (code "67") (name "unconnected-(U$2-34:GPIO22-Pad34)") (class "Default")
      (node (ref "U$2") (pin "34") (pinfunction "34:GPIO22_34") (pintype "bidirectional"))
    )
    (net (code "68") (name "unconnected-(U$2-35:GPIO23-Pad35)") (class "Default")
      (node (ref "U$2") (pin "35") (pinfunction "35:GPIO23_35") (pintype "bidirectional"))
    )
    (net (code "69") (name "unconnected-(U$2-36:GPIO24-Pad36)") (class "Default")
      (node (ref "U$2") (pin "36") (pinfunction "36:GPIO24_36") (pintype "bidirectional"))
    )
    (net (code "70") (name "unconnected-(U$2-37:GPIO25-Pad37)") (class "Default")
      (node (ref "U$2") (pin "37") (pinfunction "37:GPIO25_37") (pintype "bidirectional"))
    )
    (net (code "71") (name "unconnected-(U$2-38:GPIO26{slash}ADC0-Pad38)") (class "Default")
      (node (ref "U$2") (pin "38") (pinfunction "38:GPIO26/ADC0_38") (pintype "bidirectional"))
    )
    (net (code "72") (name "unconnected-(U$2-39:GPIO27{slash}ADC1-Pad39)") (class "Default")
      (node (ref "U$2") (pin "39") (pinfunction "39:GPIO27/ADC1_39") (pintype "bidirectional"))
    )
    (net (code "73") (name "unconnected-(U$2-40:GPIO28{slash}ADC2-Pad40)") (class "Default")
      (node (ref "U$2") (pin "40") (pinfunction "40:GPIO28/ADC2_40") (pintype "bidirectional"))
    )
    (net (code "74") (name "unconnected-(U$2-41:GPIO29{slash}ADC3-Pad41)") (class "Default")
      (node (ref "U$2") (pin "41") (pinfunction "41:GPIO29/ADC3_41") (pintype "bidirectional"))
    )
    (net (code "75") (name "unconnected-(U$6-SBU1-PadA8:SBU1)") (class "Default")
      (node (ref "U$6") (pin "A8:SBU1") (pinfunction "SBU1_A8:SBU1") (pintype "bidirectional"))
    )
    (net (code "76") (name "unconnected-(U$6-SBU2-PadB8:SBU2)") (class "Default")
      (node (ref "U$6") (pin "B8:SBU2") (pinfunction "SBU2_B8:SBU2") (pintype "bidirectional"))
    )
  )
)
